# Pinguino-PIC18F2550.net
KiCad netlist of a schematic drawn in EAGLE
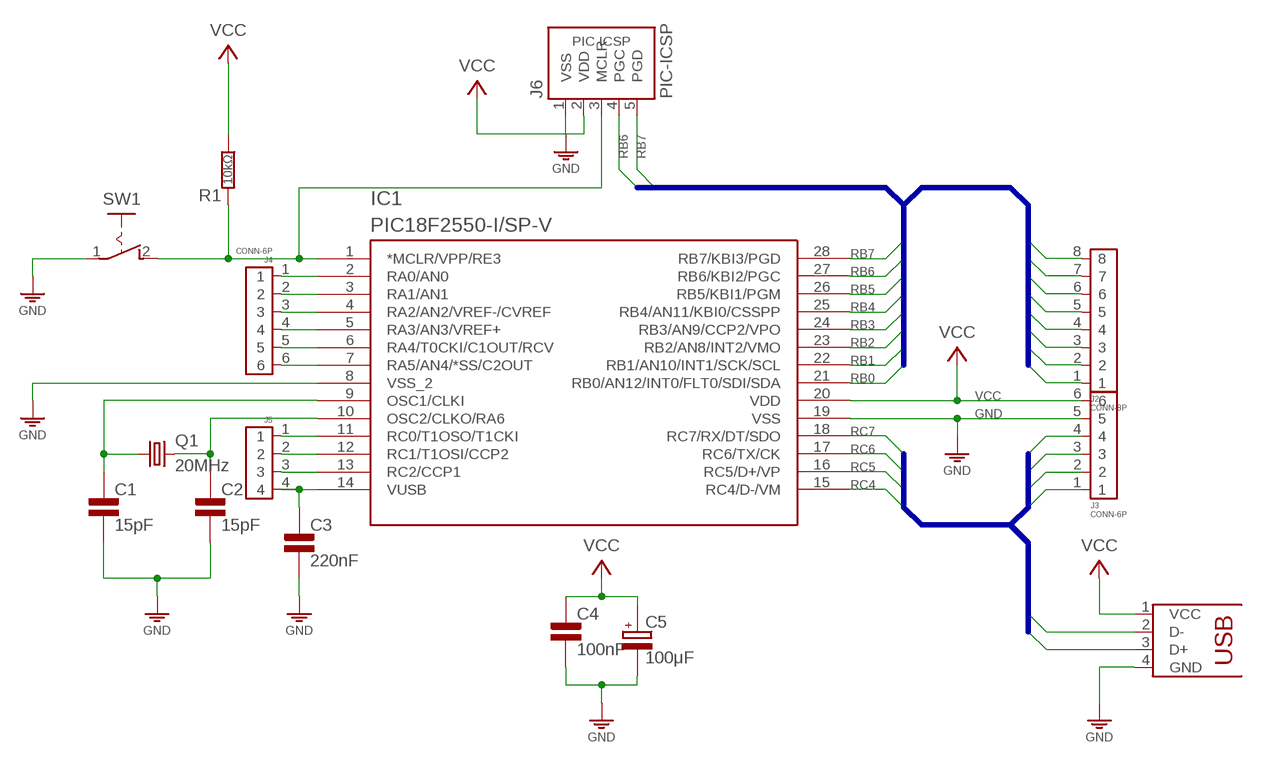
[diagram p0: schematic, sheet 1]

(export (version "E")
  (design (tool "Eeschema 10.0.6"))
  (components
    (comp (ref "C1")
      (value "15pF")
      (footprint "eagle-import:C025-015X024")
      (libsource (lib "eagle-import") (part "C025-015X024"))
    )
    (comp (ref "C2")
      (value "15pF")
      (footprint "eagle-import:C025-015X024")
      (libsource (lib "eagle-import") (part "C025-015X024"))
    )
    (comp (ref "C3")
      (value "220nF")
      (footprint "eagle-import:C075-032X103")
      (libsource (lib "eagle-import") (part "C075-032X103"))
    )
    (comp (ref "C4")
      (value "100nF")
      (footprint "eagle-import:C025-015X024")
      (libsource (lib "eagle-import") (part "C025-015X024"))
    )
    (comp (ref "C5")
      (value "100μF")
      (footprint "eagle-import:E2,5-4")
      (libsource (lib "eagle-import") (part "CPOLE2,5-4"))
    )
    (comp (ref "IC1")
      (value "PIC18F2550-I/SP-V")
      (footprint "eagle-import:DIL28-3_V")
      (libsource (lib "eagle-import") (part "PIC18F2550-I/SP-V"))
    )
    (comp (ref "J1")
      (value "USB-PRINT")
      (footprint "eagle-import:USB-B-PRINT")
      (libsource (lib "eagle-import") (part "USB-PRINT"))
    )
    (comp (ref "J2")
      (value "CONN-8P")
      (footprint "eagle-import:CONN-8P")
      (libsource (lib "eagle-import") (part "CONN-8P"))
    )
    (comp (ref "J3")
      (value "CONN-6P")
      (footprint "eagle-import:CONN-6P")
      (libsource (lib "eagle-import") (part "CONN-6P"))
    )
    (comp (ref "J4")
      (value "CONN-6P")
      (footprint "eagle-import:CONN-6P")
      (libsource (lib "eagle-import") (part "CONN-6P"))
    )
    (comp (ref "J5")
      (value "CONN-4P-4P")
      (footprint "eagle-import:CONN-4P")
      (libsource (lib "eagle-import") (part "CONN-4P-4P"))
    )
    (comp (ref "J6")
      (value "PIC-ICSP")
      (footprint "eagle-import:CONN-5P")
      (libsource (lib "eagle-import") (part "PIC-ICSP"))
    )
    (comp (ref "J8")
      (value "VCC_GNDPWR-R")
      (footprint "eagle-import:PWR-R")
      (libsource (lib "eagle-import") (part "VCC_GNDPWR-R"))
    )
    (comp (ref "Q1")
      (value "20MHz")
      (footprint "eagle-import:HC49")
      (libsource (lib "eagle-import") (part "CRYSTALHC49"))
    )
    (comp (ref "R1")
      (value "10kΩ")
      (footprint "eagle-import:0204_10")
      (libsource (lib "eagle-import") (part "R0204/10"))
    )
    (comp (ref "SW1")
      (value "PB-1P-1T")
      (footprint "eagle-import:PB-1P1T")
      (libsource (lib "eagle-import") (part "PB-1P-1T"))
    )
  )
  (nets
    (net (code "1") (name "/RB0") (class "Default")
      (node (ref "IC1") (pin "21") (pinfunction "RB0/AN12/INT0/FLT0/SDI/SDA_21") (pintype "passive"))
      (node (ref "J2") (pin "1") (pinfunction "1_1") (pintype "passive"))
    )
    (net (code "2") (name "/RB1") (class "Default")
      (node (ref "IC1") (pin "22") (pinfunction "RB1/AN10/INT1/SCK/SCL_22") (pintype "passive"))
      (node (ref "J2") (pin "2") (pinfunction "2_2") (pintype "passive"))
    )
    (net (code "3") (name "/RB2") (class "Default")
      (node (ref "IC1") (pin "23") (pinfunction "RB2/AN8/INT2/VMO_23") (pintype "passive"))
      (node (ref "J2") (pin "3") (pinfunction "3_3") (pintype "passive"))
    )
    (net (code "4") (name "/RB3") (class "Default")
      (node (ref "IC1") (pin "24") (pinfunction "RB3/AN9/CCP2/VPO_24") (pintype "passive"))
      (node (ref "J2") (pin "4") (pinfunction "4_4") (pintype "passive"))
    )
    (net (code "5") (name "/RB4") (class "Default")
      (node (ref "IC1") (pin "25") (pinfunction "RB4/AN11/KBI0/CSSPP_25") (pintype "passive"))
      (node (ref "J2") (pin "5") (pinfunction "5_5") (pintype "passive"))
    )
    (net (code "6") (name "/RB5") (class "Default")
      (node (ref "IC1") (pin "26") (pinfunction "RB5/KBI1/PGM_26") (pintype "passive"))
      (node (ref "J2") (pin "6") (pinfunction "6_6") (pintype "passive"))
    )
    (net (code "7") (name "/RB6") (class "Default")
      (node (ref "IC1") (pin "27") (pinfunction "RB6/KBI2/PGC_27") (pintype "passive"))
      (node (ref "J2") (pin "7") (pinfunction "7_7") (pintype "passive"))
      (node (ref "J6") (pin "4") (pinfunction "PGC_4") (pintype "passive"))
    )
    (net (code "8") (name "/RB7") (class "Default")
      (node (ref "IC1") (pin "28") (pinfunction "RB7/KBI3/PGD_28") (pintype "passive"))
      (node (ref "J2") (pin "8") (pinfunction "8_8") (pintype "passive"))
      (node (ref "J6") (pin "5") (pinfunction "PGD_5") (pintype "passive"))
    )
    (net (code "9") (name "/RC4") (class "Default")
      (node (ref "IC1") (pin "15") (pinfunction "RC4/D-/VM_15") (pintype "passive"))
      (node (ref "J1") (pin "3") (pinfunction "D+_3") (pintype "bidirectional"))
      (node (ref "J3") (pin "1") (pinfunction "1_1") (pintype "passive"))
    )
    (net (code "10") (name "/RC5") (class "Default")
      (node (ref "IC1") (pin "16") (pinfunction "RC5/D+/VP_16") (pintype "passive"))
      (node (ref "J1") (pin "2") (pinfunction "D-_2") (pintype "bidirectional"))
      (node (ref "J3") (pin "2") (pinfunction "2_2") (pintype "passive"))
    )
    (net (code "11") (name "/RC6") (class "Default")
      (node (ref "IC1") (pin "17") (pinfunction "RC6/TX/CK_17") (pintype "passive"))
      (node (ref "J3") (pin "3") (pinfunction "3_3") (pintype "passive"))
    )
    (net (code "12") (name "/RC7") (class "Default")
      (node (ref "IC1") (pin "18") (pinfunction "RC7/RX/DT/SDO_18") (pintype "passive"))
      (node (ref "J3") (pin "4") (pinfunction "4_4") (pintype "passive"))
    )
    (net (code "13") (name "GND") (class "Default")
      (node (ref "C1") (pin "2") (pinfunction "2_2") (pintype "passive"))
      (node (ref "C2") (pin "2") (pinfunction "2_2") (pintype "passive"))
      (node (ref "C3") (pin "2") (pinfunction "2_2") (pintype "passive"))
      (node (ref "C4") (pin "2") (pinfunction "2_2") (pintype "passive"))
      (node (ref "C5") (pin "-") (pinfunction "-_-") (pintype "passive"))
      (node (ref "IC1") (pin "19") (pinfunction "VSS_19") (pintype "passive"))
      (node (ref "IC1") (pin "8") (pinfunction "VSS_2_8") (pintype "passive"))
      (node (ref "J1") (pin "4") (pinfunction "GND_4") (pintype "bidirectional"))
      (node (ref "J3") (pin "5") (pinfunction "5_5") (pintype "passive"))
      (node (ref "J6") (pin "1") (pinfunction "VSS_1") (pintype "passive"))
      (node (ref "J8") (pin "1") (pinfunction "GND_1") (pintype "power_in"))
      (node (ref "SW1") (pin "1") (pinfunction "P_1") (pintype "passive"))
    )
    (net (code "14") (name "Net-(IC1-*MCLR{slash}VPP{slash}RE3)") (class "Default")
      (node (ref "IC1") (pin "1") (pinfunction "*MCLR/VPP/RE3_1") (pintype "passive"))
      (node (ref "J6") (pin "3") (pinfunction "MCLR_3") (pintype "passive"))
      (node (ref "R1") (pin "2") (pinfunction "2_2") (pintype "passive"))
      (node (ref "SW1") (pin "2") (pinfunction "S_2") (pintype "passive"))
    )
    (net (code "15") (name "Net-(IC1-OSC1{slash}CLKI)") (class "Default")
      (node (ref "C1") (pin "1") (pinfunction "1_1") (pintype "passive"))
      (node (ref "IC1") (pin "9") (pinfunction "OSC1/CLKI_9") (pintype "passive"))
      (node (ref "Q1") (pin "1") (pinfunction "1_1") (pintype "passive"))
    )
    (net (code "16") (name "Net-(IC1-OSC2{slash}CLKO{slash}RA6)") (class "Default")
      (node (ref "C2") (pin "1") (pinfunction "1_1") (pintype "passive"))
      (node (ref "IC1") (pin "10") (pinfunction "OSC2/CLKO/RA6_10") (pintype "passive"))
      (node (ref "Q1") (pin "2") (pinfunction "2_2") (pintype "passive"))
    )
    (net (code "17") (name "Net-(IC1-RA0{slash}AN0)") (class "Default")
      (node (ref "IC1") (pin "2") (pinfunction "RA0/AN0_2") (pintype "passive"))
      (node (ref "J4") (pin "1") (pinfunction "1_1") (pintype "passive"))
    )
    (net (code "18") (name "Net-(IC1-RA1{slash}AN1)") (class "Default")
      (node (ref "IC1") (pin "3") (pinfunction "RA1/AN1_3") (pintype "passive"))
      (node (ref "J4") (pin "2") (pinfunction "2_2") (pintype "passive"))
    )
    (net (code "19") (name "Net-(IC1-RA2{slash}AN2{slash}VREF-{slash}CVREF)") (class "Default")
      (node (ref "IC1") (pin "4") (pinfunction "RA2/AN2/VREF-/CVREF_4") (pintype "passive"))
      (node (ref "J4") (pin "3") (pinfunction "3_3") (pintype "passive"))
    )
    (net (code "20") (name "Net-(IC1-RA3{slash}AN3{slash}VREF+)") (class "Default")
      (node (ref "IC1") (pin "5") (pinfunction "RA3/AN3/VREF+_5") (pintype "passive"))
      (node (ref "J4") (pin "4") (pinfunction "4_4") (pintype "passive"))
    )
    (net (code "21") (name "Net-(IC1-RA4{slash}T0CKI{slash}C1OUT{slash}RCV)") (class "Default")
      (node (ref "IC1") (pin "6") (pinfunction "RA4/T0CKI/C1OUT/RCV_6") (pintype "passive"))
      (node (ref "J4") (pin "5") (pinfunction "5_5") (pintype "passive"))
    )
    (net (code "22") (name "Net-(IC1-RA5{slash}AN4{slash}*SS{slash}C2OUT)") (class "Default")
      (node (ref "IC1") (pin "7") (pinfunction "RA5/AN4/*SS/C2OUT_7") (pintype "passive"))
      (node (ref "J4") (pin "6") (pinfunction "6_6") (pintype "passive"))
    )
    (net (code "23") (name "Net-(IC1-RC0{slash}T1OSO{slash}T1CKI)") (class "Default")
      (node (ref "IC1") (pin "11") (pinfunction "RC0/T1OSO/T1CKI_11") (pintype "passive"))
      (node (ref "J5") (pin "1") (pinfunction "1_1") (pintype "bidirectional"))
    )
    (net (code "24") (name "Net-(IC1-RC1{slash}T1OSI{slash}CCP2)") (class "Default")
      (node (ref "IC1") (pin "12") (pinfunction "RC1/T1OSI/CCP2_12") (pintype "passive"))
      (node (ref "J5") (pin "2") (pinfunction "2_2") (pintype "bidirectional"))
    )
    (net (code "25") (name "Net-(IC1-RC2{slash}CCP1)") (class "Default")
      (node (ref "IC1") (pin "13") (pinfunction "RC2/CCP1_13") (pintype "passive"))
      (node (ref "J5") (pin "3") (pinfunction "3_3") (pintype "bidirectional"))
    )
    (net (code "26") (name "Net-(IC1-VUSB)") (class "Default")
      (node (ref "C3") (pin "1") (pinfunction "1_1") (pintype "passive"))
      (node (ref "IC1") (pin "14") (pinfunction "VUSB_14") (pintype "passive"))
      (node (ref "J5") (pin "4") (pinfunction "4_4") (pintype "bidirectional"))
    )
    (net (code "27") (name "VCC") (class "Default")
      (node (ref "C4") (pin "1") (pinfunction "1_1") (pintype "passive"))
      (node (ref "C5") (pin "+") (pinfunction "+_+") (pintype "passive"))
      (node (ref "IC1") (pin "20") (pinfunction "VDD_20") (pintype "passive"))
      (node (ref "J1") (pin "1") (pinfunction "VCC_1") (pintype "bidirectional"))
      (node (ref "J3") (pin "6") (pinfunction "6_6") (pintype "passive"))
      (node (ref "J6") (pin "2") (pinfunction "VDD_2") (pintype "passive"))
      (node (ref "J8") (pin "2") (pinfunction "VCC_2") (pintype "power_in"))
      (node (ref "R1") (pin "1") (pinfunction "1_1") (pintype "passive"))
    )
  )
)
